# RPi0PWR2.net
KiCad netlist of a schematic drawn in EAGLE
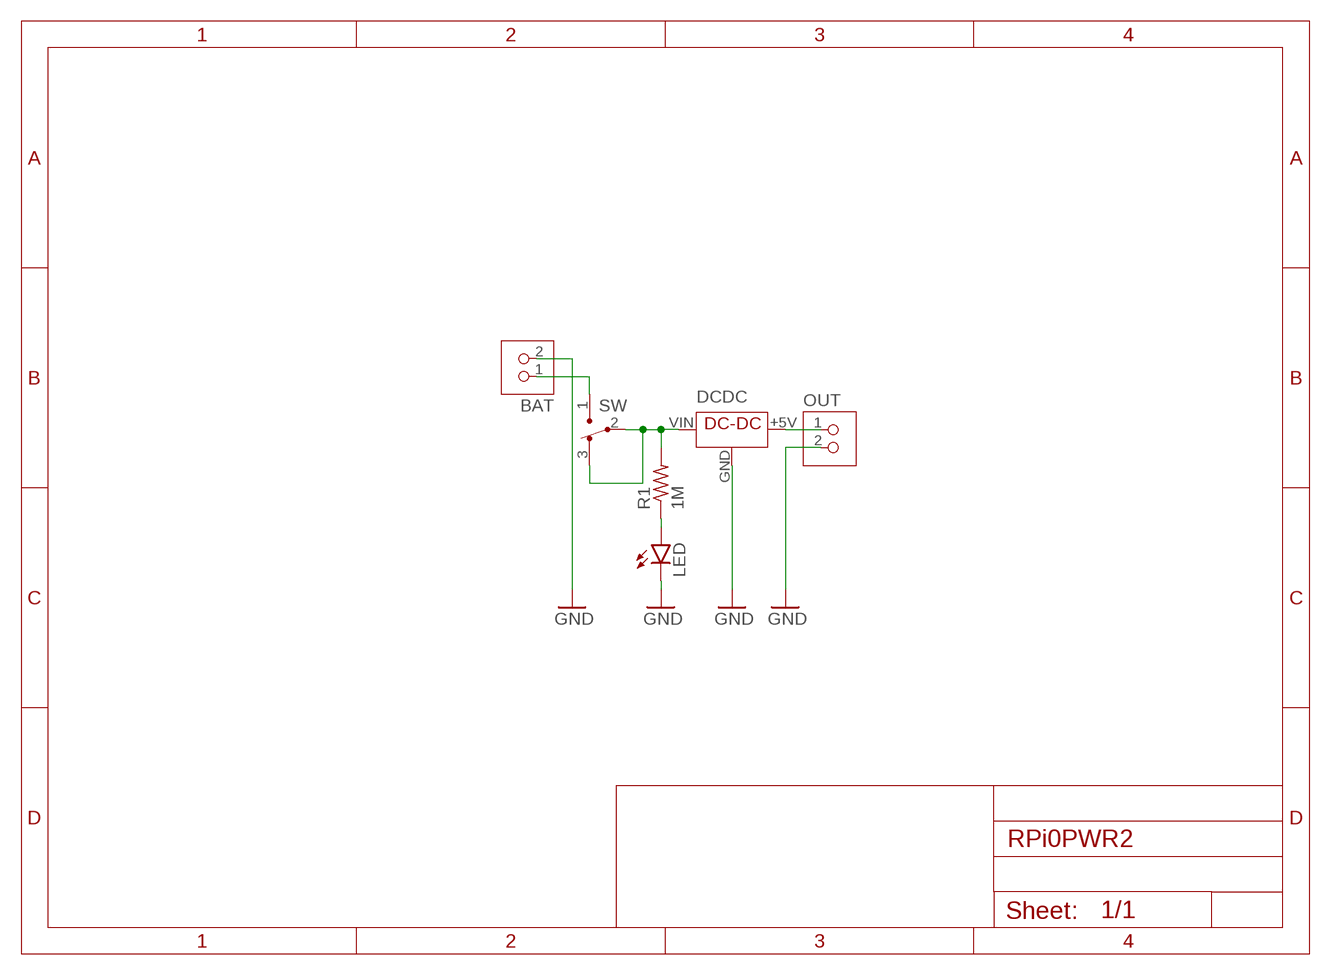
[diagram p0: schematic, sheet 1]

(export (version "E")
  (design (tool "Eeschema 10.0.6"))
  (components
    (comp (ref "BAT")
      (value "JST-PH2")
      (footprint "eagle-import:JST-PH2")
      (libsource (lib "eagle-import") (part "JST-PH2"))
    )
    (comp (ref "DCDC")
      (value "DCDC-5V-0.48A")
      (footprint "eagle-import:DCDC-5V-0.48A")
      (libsource (lib "eagle-import") (part "DCDC-5V-0.48A"))
    )
    (comp (ref "LED")
      (value "LED3MM")
      (footprint "eagle-import:LED3MM")
      (libsource (lib "eagle-import") (part "LED3MM"))
    )
    (comp (ref "OUT")
      (value "JST-PH2")
      (footprint "eagle-import:JST-PH2")
      (libsource (lib "eagle-import") (part "JST-PH2"))
    )
    (comp (ref "R1")
      (value "1M")
      (footprint "eagle-import:0204_5")
      (libsource (lib "eagle-import") (part "R-US_0204/5"))
    )
    (comp (ref "SW")
      (value "SW3-1")
      (footprint "eagle-import:SW3-1")
      (fields (field (name "MF") "HiLetgo"))
      (libsource (lib "eagle-import") (part "SW3-1"))
    )
  )
  (nets
    (net (code "1") (name "GND") (class "Default")
      (node (ref "BAT") (pin "2") (pinfunction "2_2") (pintype "passive"))
      (node (ref "DCDC") (pin "GND") (pinfunction "GND_GND") (pintype "power_in"))
      (node (ref "LED") (pin "K") (pinfunction "C_K") (pintype "passive"))
      (node (ref "OUT") (pin "2") (pinfunction "2_2") (pintype "passive"))
    )
    (net (code "2") (name "Net-(BAT-Pad1)") (class "Default")
      (node (ref "BAT") (pin "1") (pinfunction "1_1") (pintype "passive"))
      (node (ref "SW") (pin "1") (pinfunction "1_1") (pintype "passive"))
    )
    (net (code "3") (name "Net-(DCDC-PadVIN)") (class "Default")
      (node (ref "DCDC") (pin "VIN") (pinfunction "VIN_VIN") (pintype "power_in"))
      (node (ref "R1") (pin "2") (pinfunction "2_2") (pintype "passive"))
      (node (ref "SW") (pin "2") (pinfunction "2_2") (pintype "passive"))
      (node (ref "SW") (pin "3") (pinfunction "3_3") (pintype "passive"))
    )
    (net (code "4") (name "Net-(DCDC-VOUT)") (class "Default")
      (node (ref "DCDC") (pin "+5V") (pinfunction "VOUT_+5V") (pintype "power_in"))
      (node (ref "OUT") (pin "1") (pinfunction "1_1") (pintype "passive"))
    )
    (net (code "5") (name "Net-(LED-PadA)") (class "Default")
      (node (ref "LED") (pin "A") (pinfunction "A_A") (pintype "passive"))
      (node (ref "R1") (pin "1") (pinfunction "1_1") (pintype "passive"))
    )
  )
)
